# PWMControl.net
KiCad netlist of a schematic drawn in Altium Designer
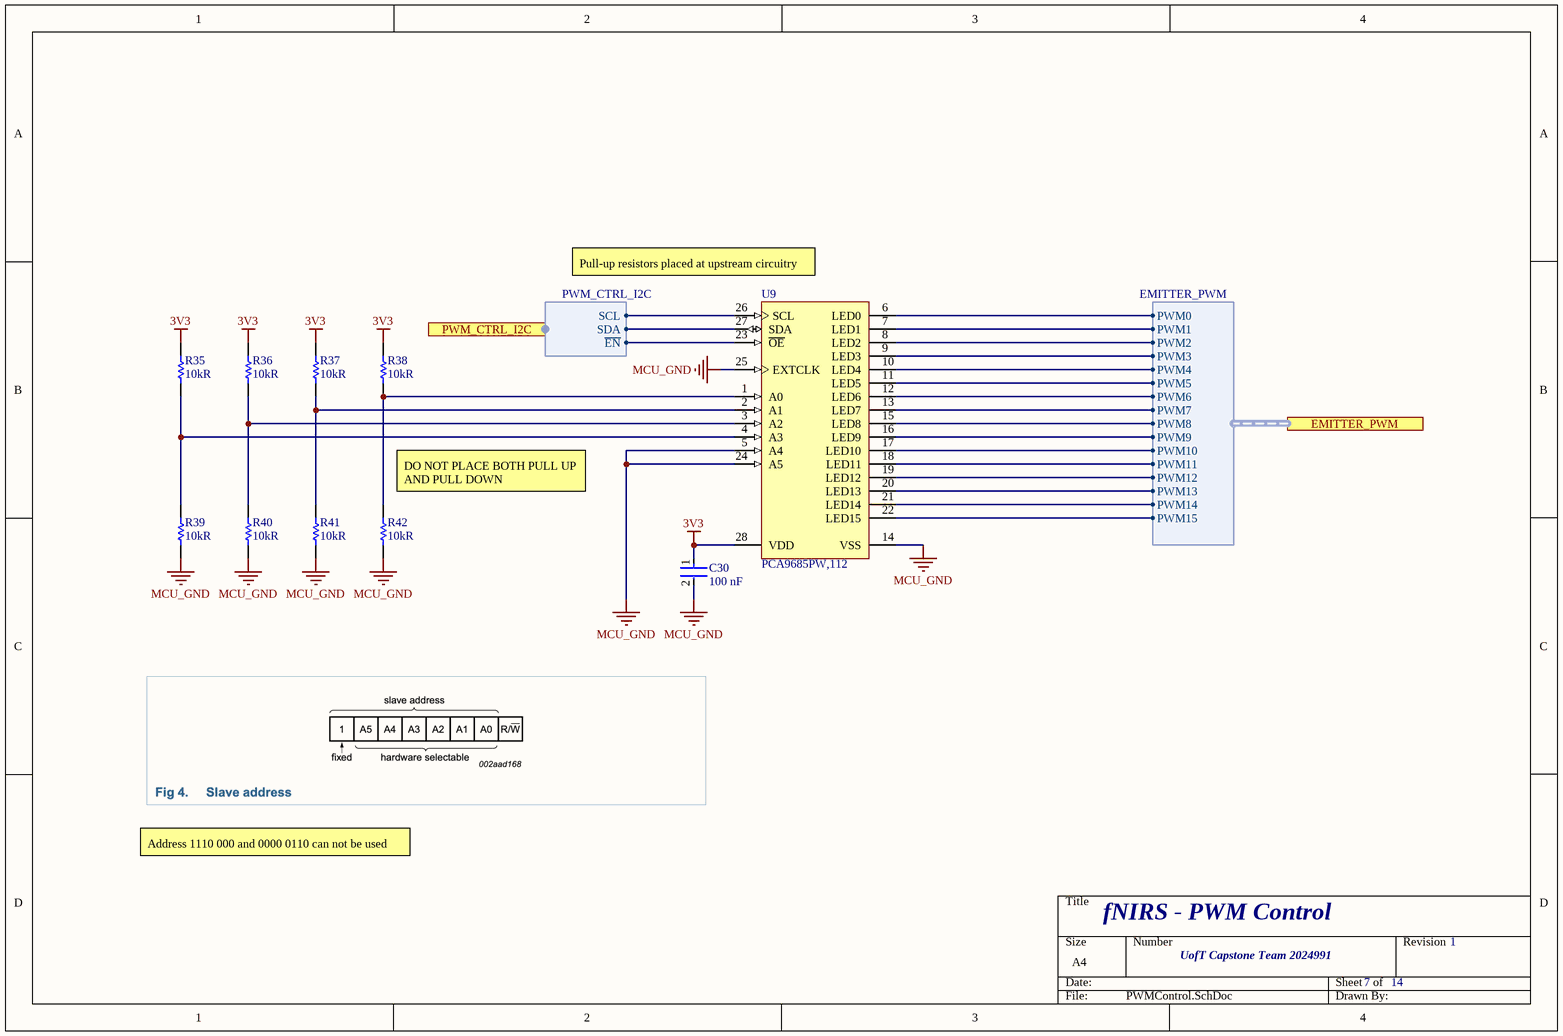
[diagram p0: PWMControl.SchDoc]

(export (version "E")
  (design (tool "Eeschema 10.0.6"))
  (components
    (comp (ref "C30")
      (value "CC0603KRX7R7BB104")
      (footprint "FP-CC0603-DA-MFG")
      (description "CAP CER 0.1UF 16V X7R 0603")
      (fields
        (field (name "OCTOPART") "https://octopart.com/cc0603krx7r7bb104-yageo-192941")
        (field (name "TOLERANCE") "0.1")
        (field (name "CAPACITANCE") "100 nF")
      )
      (libsource (lib "Altium Content Vault") (part "11868f565c42a9108669ba33697ecf6"))
    )
    (comp (ref "R35")
      (value "CRCW060310K0FKEA")
      (footprint "RESC1609X50X30NL8T20")
      (description "Chip Resistor, 10 KOhm, +/- 1%, 100 mW, -55 to 155 degC, 0603 (1608 Metric), RoHS, Tape and Reel")
      (fields (field (name "MANUFACTURER") "Vishay Semiconductor") (field (name "RESISTANCE") "10kR"))
      (libsource (lib "Altium Content Vault") (part "RES-2"))
    )
    (comp (ref "R36")
      (value "CRCW060310K0FKEA")
      (footprint "RESC1609X50X30NL8T20")
      (description "Chip Resistor, 10 KOhm, +/- 1%, 100 mW, -55 to 155 degC, 0603 (1608 Metric), RoHS, Tape and Reel")
      (fields (field (name "MANUFACTURER") "Vishay Semiconductor") (field (name "RESISTANCE") "10kR"))
      (libsource (lib "Altium Content Vault") (part "RES-2"))
    )
    (comp (ref "R37")
      (value "CRCW060310K0FKEA")
      (footprint "RESC1609X50X30NL8T20")
      (description "Chip Resistor, 10 KOhm, +/- 1%, 100 mW, -55 to 155 degC, 0603 (1608 Metric), RoHS, Tape and Reel")
      (fields (field (name "MANUFACTURER") "Vishay Semiconductor") (field (name "RESISTANCE") "10kR"))
      (libsource (lib "Altium Content Vault") (part "RES-2"))
    )
    (comp (ref "R38")
      (value "CRCW060310K0FKEA")
      (footprint "RESC1609X50X30NL8T20")
      (description "Chip Resistor, 10 KOhm, +/- 1%, 100 mW, -55 to 155 degC, 0603 (1608 Metric), RoHS, Tape and Reel")
      (fields (field (name "MANUFACTURER") "Vishay Semiconductor") (field (name "RESISTANCE") "10kR"))
      (libsource (lib "Altium Content Vault") (part "RES-2"))
    )
    (comp (ref "R39")
      (value "CRCW060310K0FKEA")
      (footprint "RESC1609X50X30NL8T20")
      (description "Chip Resistor, 10 KOhm, +/- 1%, 100 mW, -55 to 155 degC, 0603 (1608 Metric), RoHS, Tape and Reel")
      (fields (field (name "MANUFACTURER") "Vishay Semiconductor") (field (name "RESISTANCE") "10kR"))
      (libsource (lib "Altium Content Vault") (part "RES-2"))
    )
    (comp (ref "R40")
      (value "CRCW060310K0FKEA")
      (footprint "RESC1609X50X30NL8T20")
      (description "Chip Resistor, 10 KOhm, +/- 1%, 100 mW, -55 to 155 degC, 0603 (1608 Metric), RoHS, Tape and Reel")
      (fields (field (name "MANUFACTURER") "Vishay Semiconductor") (field (name "RESISTANCE") "10kR"))
      (libsource (lib "Altium Content Vault") (part "RES-2"))
    )
    (comp (ref "R41")
      (value "CRCW060310K0FKEA")
      (footprint "RESC1609X50X30NL8T20")
      (description "Chip Resistor, 10 KOhm, +/- 1%, 100 mW, -55 to 155 degC, 0603 (1608 Metric), RoHS, Tape and Reel")
      (fields (field (name "MANUFACTURER") "Vishay Semiconductor") (field (name "RESISTANCE") "10kR"))
      (libsource (lib "Altium Content Vault") (part "RES-2"))
    )
    (comp (ref "R42")
      (value "CRCW060310K0FKEA")
      (footprint "RESC1609X50X30NL8T20")
      (description "Chip Resistor, 10 KOhm, +/- 1%, 100 mW, -55 to 155 degC, 0603 (1608 Metric), RoHS, Tape and Reel")
      (fields (field (name "MANUFACTURER") "Vishay Semiconductor") (field (name "RESISTANCE") "10kR"))
      (libsource (lib "Altium Content Vault") (part "RES-2"))
    )
    (comp (ref "U9")
      (value "PCA9685PW,112")
      (footprint "SOT361-1_V")
      (fields (field (name "PARTNUMBER") "PCA9685"))
      (libsource (lib "Altium Content Vault") (part "NXP-PCA9685-SOT361-1"))
    )
  )
  (nets
    (net (code "3") (name "/PWM0") (class "Default")
      (node (ref "U9") (pin "6") (pinfunction "LED0_6") (pintype "tri_state"))
    )
    (net (code "4") (name "/PWM1") (class "Default")
      (node (ref "U9") (pin "7") (pinfunction "LED1_7") (pintype "tri_state"))
    )
    (net (code "5") (name "/PWM2") (class "Default")
      (node (ref "U9") (pin "8") (pinfunction "LED2_8") (pintype "tri_state"))
    )
    (net (code "6") (name "/PWM3") (class "Default")
      (node (ref "U9") (pin "9") (pinfunction "LED3_9") (pintype "tri_state"))
    )
    (net (code "7") (name "/PWM4") (class "Default")
      (node (ref "U9") (pin "10") (pinfunction "LED4_10") (pintype "tri_state"))
    )
    (net (code "8") (name "/PWM5") (class "Default")
      (node (ref "U9") (pin "11") (pinfunction "LED5_11") (pintype "tri_state"))
    )
    (net (code "9") (name "/PWM6") (class "Default")
      (node (ref "U9") (pin "12") (pinfunction "LED6_12") (pintype "tri_state"))
    )
    (net (code "10") (name "/PWM7") (class "Default")
      (node (ref "U9") (pin "13") (pinfunction "LED7_13") (pintype "tri_state"))
    )
    (net (code "11") (name "/PWM8") (class "Default")
      (node (ref "U9") (pin "15") (pinfunction "LED8_15") (pintype "tri_state"))
    )
    (net (code "12") (name "/PWM9") (class "Default")
      (node (ref "U9") (pin "16") (pinfunction "LED9_16") (pintype "tri_state"))
    )
    (net (code "13") (name "/PWM10") (class "Default")
      (node (ref "U9") (pin "17") (pinfunction "LED10_17") (pintype "tri_state"))
    )
    (net (code "14") (name "/PWM11") (class "Default")
      (node (ref "U9") (pin "18") (pinfunction "LED11_18") (pintype "tri_state"))
    )
    (net (code "15") (name "/PWM12") (class "Default")
      (node (ref "U9") (pin "19") (pinfunction "LED12_19") (pintype "tri_state"))
    )
    (net (code "16") (name "/PWM13") (class "Default")
      (node (ref "U9") (pin "20") (pinfunction "LED13_20") (pintype "tri_state"))
    )
    (net (code "17") (name "/PWM14") (class "Default")
      (node (ref "U9") (pin "21") (pinfunction "LED14_21") (pintype "tri_state"))
    )
    (net (code "18") (name "/PWM15") (class "Default")
      (node (ref "U9") (pin "22") (pinfunction "LED15_22") (pintype "tri_state"))
    )
    (net (code "19") (name "/SCL") (class "Default")
      (node (ref "U9") (pin "26") (pinfunction "SCL_26") (pintype "input"))
    )
    (net (code "20") (name "/SDA") (class "Default")
      (node (ref "U9") (pin "27") (pinfunction "SDA_27") (pintype "bidirectional"))
    )
    (net (code "23") (name "/~{EN}") (class "Default")
      (node (ref "U9") (pin "23") (pinfunction "~{OE}_23") (pintype "input"))
    )
    (net (code "24") (name "3V3") (class "Default")
      (node (ref "C30") (pin "1") (pinfunction "1_1") (pintype "passive"))
      (node (ref "R35") (pin "2") (pinfunction "2_2") (pintype "passive"))
      (node (ref "R36") (pin "2") (pinfunction "2_2") (pintype "passive"))
      (node (ref "R37") (pin "2") (pinfunction "2_2") (pintype "passive"))
      (node (ref "R38") (pin "2") (pinfunction "2_2") (pintype "passive"))
      (node (ref "U9") (pin "28") (pinfunction "VDD_28") (pintype "power_in"))
    )
    (net (code "25") (name "MCU_GND") (class "Default")
      (node (ref "C30") (pin "2") (pinfunction "2_2") (pintype "passive"))
      (node (ref "R39") (pin "1") (pinfunction "1_1") (pintype "passive"))
      (node (ref "R40") (pin "1") (pinfunction "1_1") (pintype "passive"))
      (node (ref "R41") (pin "1") (pinfunction "1_1") (pintype "passive"))
      (node (ref "R42") (pin "1") (pinfunction "1_1") (pintype "passive"))
      (node (ref "U9") (pin "14") (pinfunction "VSS_14") (pintype "power_in"))
      (node (ref "U9") (pin "24") (pinfunction "A5_24") (pintype "input"))
      (node (ref "U9") (pin "25") (pinfunction "EXTCLK_25") (pintype "input"))
      (node (ref "U9") (pin "5") (pinfunction "A4_5") (pintype "input"))
    )
    (net (code "26") (name "Net-(U9-A0)") (class "Default")
      (node (ref "R38") (pin "1") (pinfunction "1_1") (pintype "passive"))
      (node (ref "R42") (pin "2") (pinfunction "2_2") (pintype "passive"))
      (node (ref "U9") (pin "1") (pinfunction "A0_1") (pintype "input"))
    )
    (net (code "27") (name "Net-(U9-A1)") (class "Default")
      (node (ref "R37") (pin "1") (pinfunction "1_1") (pintype "passive"))
      (node (ref "R41") (pin "2") (pinfunction "2_2") (pintype "passive"))
      (node (ref "U9") (pin "2") (pinfunction "A1_2") (pintype "input"))
    )
    (net (code "28") (name "Net-(U9-A2)") (class "Default")
      (node (ref "R36") (pin "1") (pinfunction "1_1") (pintype "passive"))
      (node (ref "R40") (pin "2") (pinfunction "2_2") (pintype "passive"))
      (node (ref "U9") (pin "3") (pinfunction "A2_3") (pintype "input"))
    )
    (net (code "29") (name "Net-(U9-A3)") (class "Default")
      (node (ref "R35") (pin "1") (pinfunction "1_1") (pintype "passive"))
      (node (ref "R39") (pin "2") (pinfunction "2_2") (pintype "passive"))
      (node (ref "U9") (pin "4") (pinfunction "A3_4") (pintype "input"))
    )
  )
)
